# LEDs.net
KiCad netlist of a schematic drawn in Altium Designer
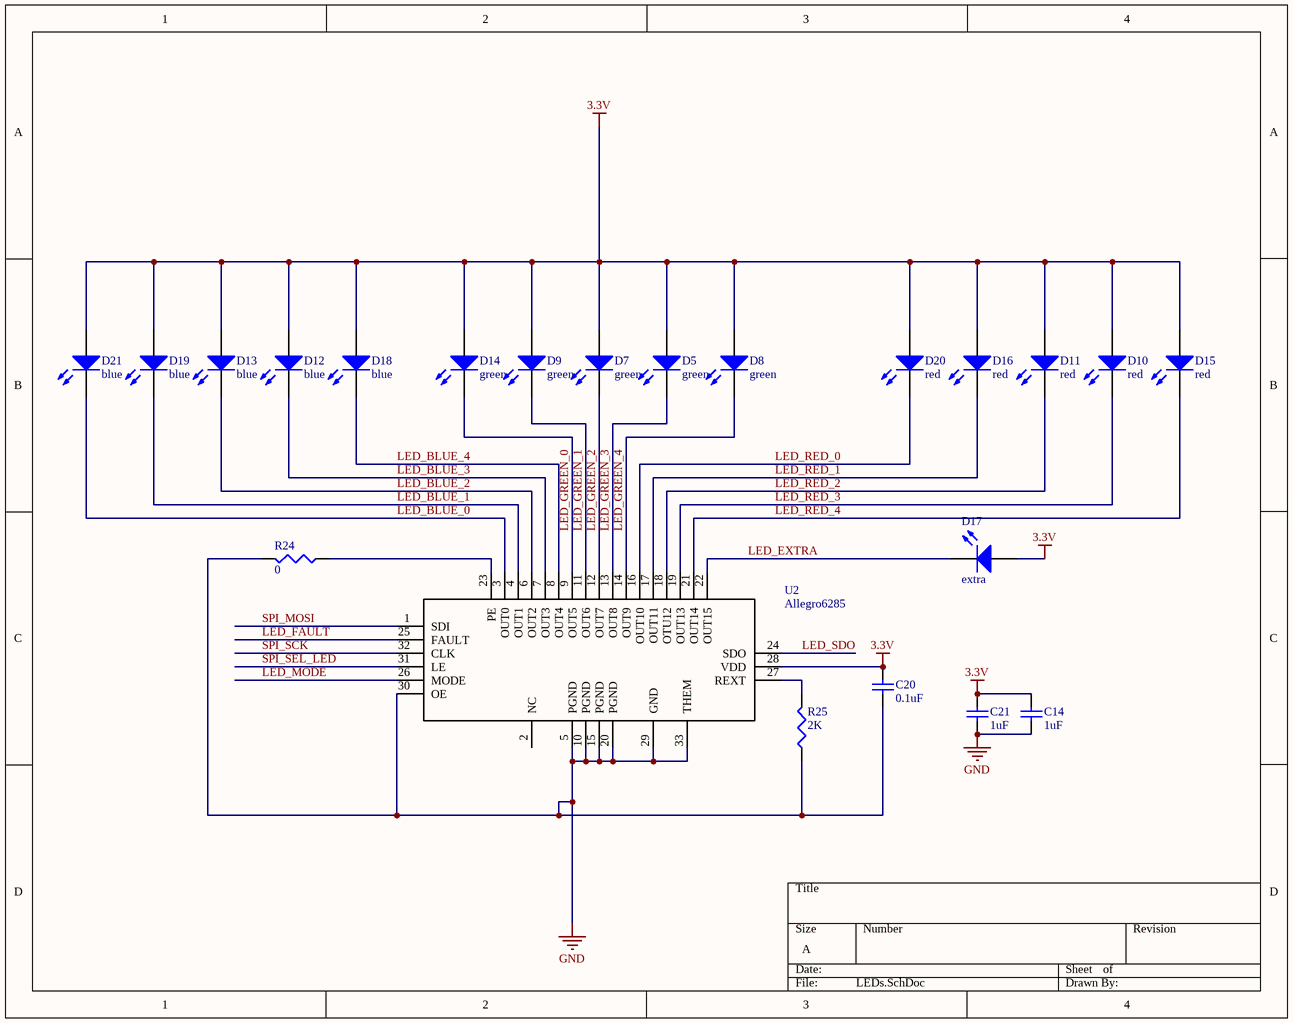
[diagram p0: LEDs.SchDoc]

(export (version "E")
  (design (tool "Eeschema 10.0.6"))
  (components
    (comp (ref "C14")
      (value "1uF")
      (footprint "CAPC1608L")
      (description "Capacitor (Semiconductor SIM Model)")
      (fields (field (name "Comment") "Cap Semi") (field (name "PUBLISHER") "Altium Limited"))
      (libsource (lib "Miscellaneous Devices") (part "Cap Semi"))
    )
    (comp (ref "C20")
      (value "0.1uF")
      (footprint "CAPC1005L")
      (description "Capacitor (Semiconductor SIM Model)")
      (fields (field (name "Comment") "Cap Semi") (field (name "PUBLISHER") "Altium Limited"))
      (libsource (lib "Miscellaneous Devices") (part "Cap Semi"))
    )
    (comp (ref "C21")
      (value "1uF")
      (footprint "CAPC1608L")
      (description "Capacitor (Semiconductor SIM Model)")
      (fields (field (name "Comment") "Cap Semi") (field (name "PUBLISHER") "Altium Limited"))
      (libsource (lib "Miscellaneous Devices") (part "Cap Semi"))
    )
    (comp (ref "D5") (value "green") (footprint "SurfaceMount(603)") (libsource (lib "") (part "LED_1")))
    (comp (ref "D7") (value "green") (footprint "SurfaceMount(603)") (libsource (lib "") (part "LED_1")))
    (comp (ref "D8") (value "green") (footprint "SurfaceMount(603)") (libsource (lib "") (part "LED_1")))
    (comp (ref "D9") (value "green") (footprint "SurfaceMount(603)") (libsource (lib "") (part "LED_1")))
    (comp (ref "D10") (value "red") (footprint "SurfaceMount(603)") (libsource (lib "") (part "LED_1")))
    (comp (ref "D11") (value "red") (footprint "SurfaceMount(603)") (libsource (lib "") (part "LED_1")))
    (comp (ref "D12") (value "blue") (footprint "SurfaceMount(603)") (libsource (lib "") (part "LED_1")))
    (comp (ref "D13") (value "blue") (footprint "SurfaceMount(603)") (libsource (lib "") (part "LED_1")))
    (comp (ref "D14") (value "green") (footprint "SurfaceMount(603)") (libsource (lib "") (part "LED_1")))
    (comp (ref "D15") (value "red") (footprint "SurfaceMount(603)") (libsource (lib "") (part "LED_1")))
    (comp (ref "D16") (value "red") (footprint "SurfaceMount(603)") (libsource (lib "") (part "LED_1")))
    (comp (ref "D17") (value "extra") (footprint "SurfaceMount(603)") (libsource (lib "mrone") (part "LED")))
    (comp (ref "D18") (value "blue") (footprint "SurfaceMount(603)") (libsource (lib "") (part "LED_1")))
    (comp (ref "D19") (value "blue") (footprint "SurfaceMount(603)") (libsource (lib "") (part "LED_1")))
    (comp (ref "D20") (value "red") (footprint "SurfaceMount(603)") (libsource (lib "") (part "LED_1")))
    (comp (ref "D21") (value "blue") (footprint "SurfaceMount(603)") (libsource (lib "") (part "LED_1")))
    (comp (ref "R24")
      (value "0")
      (footprint "RESC1608L")
      (description "Resistor")
      (fields (field (name "Comment") "Res3") (field (name "PUBLISHER") "Altium Limited"))
      (libsource (lib "Miscellaneous Devices") (part "Res3"))
    )
    (comp (ref "R25")
      (value "2K")
      (footprint "RESC1608L")
      (description "Resistor")
      (fields (field (name "Comment") "Res3") (field (name "PUBLISHER") "Altium Limited"))
      (libsource (lib "Miscellaneous Devices") (part "Res3"))
    )
    (comp (ref "U2")
      (value "Allegro6285")
      (footprint "QFN-32")
      (libsource (lib "mrone") (part "Allegro6285"))
    )
  )
  (nets
    (net (code "1") (name "/LED_BLUE_0") (class "Default")
      (node (ref "D21") (pin "2") (pinfunction "K_2") (pintype "passive"))
      (node (ref "U2") (pin "3") (pinfunction "OUT0_3") (pintype "passive"))
    )
    (net (code "2") (name "/LED_BLUE_1") (class "Default")
      (node (ref "D19") (pin "2") (pinfunction "K_2") (pintype "passive"))
      (node (ref "U2") (pin "4") (pinfunction "OUT1_4") (pintype "passive"))
    )
    (net (code "3") (name "/LED_BLUE_2") (class "Default")
      (node (ref "D13") (pin "2") (pinfunction "K_2") (pintype "passive"))
      (node (ref "U2") (pin "6") (pinfunction "OUT2_6") (pintype "passive"))
    )
    (net (code "4") (name "/LED_BLUE_3") (class "Default")
      (node (ref "D12") (pin "2") (pinfunction "K_2") (pintype "passive"))
      (node (ref "U2") (pin "7") (pinfunction "OUT3_7") (pintype "passive"))
    )
    (net (code "5") (name "/LED_BLUE_4") (class "Default")
      (node (ref "D18") (pin "2") (pinfunction "K_2") (pintype "passive"))
      (node (ref "U2") (pin "8") (pinfunction "OUT4_8") (pintype "passive"))
    )
    (net (code "6") (name "/LED_EXTRA") (class "Default")
      (node (ref "D17") (pin "2") (pinfunction "K_2") (pintype "passive"))
      (node (ref "U2") (pin "22") (pinfunction "OUT15_22") (pintype "passive"))
    )
    (net (code "7") (name "/LED_FAULT") (class "Default")
      (node (ref "U2") (pin "25") (pinfunction "FAULT_25") (pintype "passive"))
    )
    (net (code "8") (name "/LED_GREEN_0") (class "Default")
      (node (ref "D14") (pin "2") (pinfunction "K_2") (pintype "passive"))
      (node (ref "U2") (pin "9") (pinfunction "OUT5_9") (pintype "passive"))
    )
    (net (code "9") (name "/LED_GREEN_1") (class "Default")
      (node (ref "D9") (pin "2") (pinfunction "K_2") (pintype "passive"))
      (node (ref "U2") (pin "11") (pinfunction "OUT6_11") (pintype "passive"))
    )
    (net (code "10") (name "/LED_GREEN_2") (class "Default")
      (node (ref "D7") (pin "2") (pinfunction "K_2") (pintype "passive"))
      (node (ref "U2") (pin "12") (pinfunction "OUT7_12") (pintype "passive"))
    )
    (net (code "11") (name "/LED_GREEN_3") (class "Default")
      (node (ref "D5") (pin "2") (pinfunction "K_2") (pintype "passive"))
      (node (ref "U2") (pin "13") (pinfunction "OUT8_13") (pintype "passive"))
    )
    (net (code "12") (name "/LED_GREEN_4") (class "Default")
      (node (ref "D8") (pin "2") (pinfunction "K_2") (pintype "passive"))
      (node (ref "U2") (pin "14") (pinfunction "OUT9_14") (pintype "passive"))
    )
    (net (code "13") (name "/LED_MODE") (class "Default")
      (node (ref "U2") (pin "26") (pinfunction "MODE_26") (pintype "passive"))
    )
    (net (code "14") (name "/LED_RED_0") (class "Default")
      (node (ref "D20") (pin "2") (pinfunction "K_2") (pintype "passive"))
      (node (ref "U2") (pin "16") (pinfunction "OUT10_16") (pintype "passive"))
    )
    (net (code "15") (name "/LED_RED_1") (class "Default")
      (node (ref "D16") (pin "2") (pinfunction "K_2") (pintype "passive"))
      (node (ref "U2") (pin "17") (pinfunction "OUT11_17") (pintype "passive"))
    )
    (net (code "16") (name "/LED_RED_2") (class "Default")
      (node (ref "D11") (pin "2") (pinfunction "K_2") (pintype "passive"))
      (node (ref "U2") (pin "18") (pinfunction "OTU12_18") (pintype "passive"))
    )
    (net (code "17") (name "/LED_RED_3") (class "Default")
      (node (ref "D10") (pin "2") (pinfunction "K_2") (pintype "passive"))
      (node (ref "U2") (pin "19") (pinfunction "OUT13_19") (pintype "passive"))
    )
    (net (code "18") (name "/LED_RED_4") (class "Default")
      (node (ref "D15") (pin "2") (pinfunction "K_2") (pintype "passive"))
      (node (ref "U2") (pin "21") (pinfunction "OUT14_21") (pintype "passive"))
    )
    (net (code "19") (name "/LED_SDO") (class "Default")
      (node (ref "U2") (pin "24") (pinfunction "SDO_24") (pintype "passive"))
    )
    (net (code "20") (name "/SPI_MOSI") (class "Default")
      (node (ref "U2") (pin "1") (pinfunction "SDI_1") (pintype "passive"))
    )
    (net (code "21") (name "/SPI_SCK") (class "Default")
      (node (ref "U2") (pin "32") (pinfunction "CLK_32") (pintype "passive"))
    )
    (net (code "22") (name "/SPI_SEL_LED") (class "Default")
      (node (ref "U2") (pin "31") (pinfunction "LE_31") (pintype "passive"))
    )
    (net (code "23") (name "3.3V") (class "Default")
      (node (ref "C14") (pin "2") (pinfunction "2_2") (pintype "passive"))
      (node (ref "C20") (pin "2") (pinfunction "2_2") (pintype "passive"))
      (node (ref "C21") (pin "2") (pinfunction "2_2") (pintype "passive"))
      (node (ref "D10") (pin "1") (pinfunction "A_1") (pintype "passive"))
      (node (ref "D11") (pin "1") (pinfunction "A_1") (pintype "passive"))
      (node (ref "D12") (pin "1") (pinfunction "A_1") (pintype "passive"))
      (node (ref "D13") (pin "1") (pinfunction "A_1") (pintype "passive"))
      (node (ref "D14") (pin "1") (pinfunction "A_1") (pintype "passive"))
      (node (ref "D15") (pin "1") (pinfunction "A_1") (pintype "passive"))
      (node (ref "D16") (pin "1") (pinfunction "A_1") (pintype "passive"))
      (node (ref "D17") (pin "1") (pinfunction "A_1") (pintype "passive"))
      (node (ref "D18") (pin "1") (pinfunction "A_1") (pintype "passive"))
      (node (ref "D19") (pin "1") (pinfunction "A_1") (pintype "passive"))
      (node (ref "D20") (pin "1") (pinfunction "A_1") (pintype "passive"))
      (node (ref "D21") (pin "1") (pinfunction "A_1") (pintype "passive"))
      (node (ref "D5") (pin "1") (pinfunction "A_1") (pintype "passive"))
      (node (ref "D7") (pin "1") (pinfunction "A_1") (pintype "passive"))
      (node (ref "D8") (pin "1") (pinfunction "A_1") (pintype "passive"))
      (node (ref "D9") (pin "1") (pinfunction "A_1") (pintype "passive"))
      (node (ref "U2") (pin "28") (pinfunction "VDD_28") (pintype "passive"))
    )
    (net (code "24") (name "GND") (class "Default")
      (node (ref "C14") (pin "1") (pinfunction "1_1") (pintype "passive"))
      (node (ref "C20") (pin "1") (pinfunction "1_1") (pintype "passive"))
      (node (ref "C21") (pin "1") (pinfunction "1_1") (pintype "passive"))
      (node (ref "R24") (pin "2") (pinfunction "2_2") (pintype "passive"))
      (node (ref "R25") (pin "1") (pinfunction "1_1") (pintype "passive"))
      (node (ref "U2") (pin "10") (pinfunction "PGND_10") (pintype "passive"))
      (node (ref "U2") (pin "15") (pinfunction "PGND_15") (pintype "passive"))
      (node (ref "U2") (pin "20") (pinfunction "PGND_20") (pintype "passive"))
      (node (ref "U2") (pin "29") (pinfunction "GND_29") (pintype "passive"))
      (node (ref "U2") (pin "30") (pinfunction "OE_30") (pintype "passive"))
      (node (ref "U2") (pin "33") (pinfunction "THEM_33") (pintype "passive"))
      (node (ref "U2") (pin "5") (pinfunction "PGND_5") (pintype "passive"))
    )
    (net (code "25") (name "Net-(U2-PE)") (class "Default")
      (node (ref "R24") (pin "1") (pinfunction "1_1") (pintype "passive"))
      (node (ref "U2") (pin "23") (pinfunction "PE_23") (pintype "passive"))
    )
    (net (code "26") (name "Net-(U2-REXT)") (class "Default")
      (node (ref "R25") (pin "2") (pinfunction "2_2") (pintype "passive"))
      (node (ref "U2") (pin "27") (pinfunction "REXT_27") (pintype "passive"))
    )
    (net (code "27") (name "unconnected-(U2-NC-Pad2)") (class "Default")
      (node (ref "U2") (pin "2") (pinfunction "NC_2") (pintype "passive"))
    )
  )
)
